# motobit.net
KiCad netlist of a schematic drawn in EAGLE
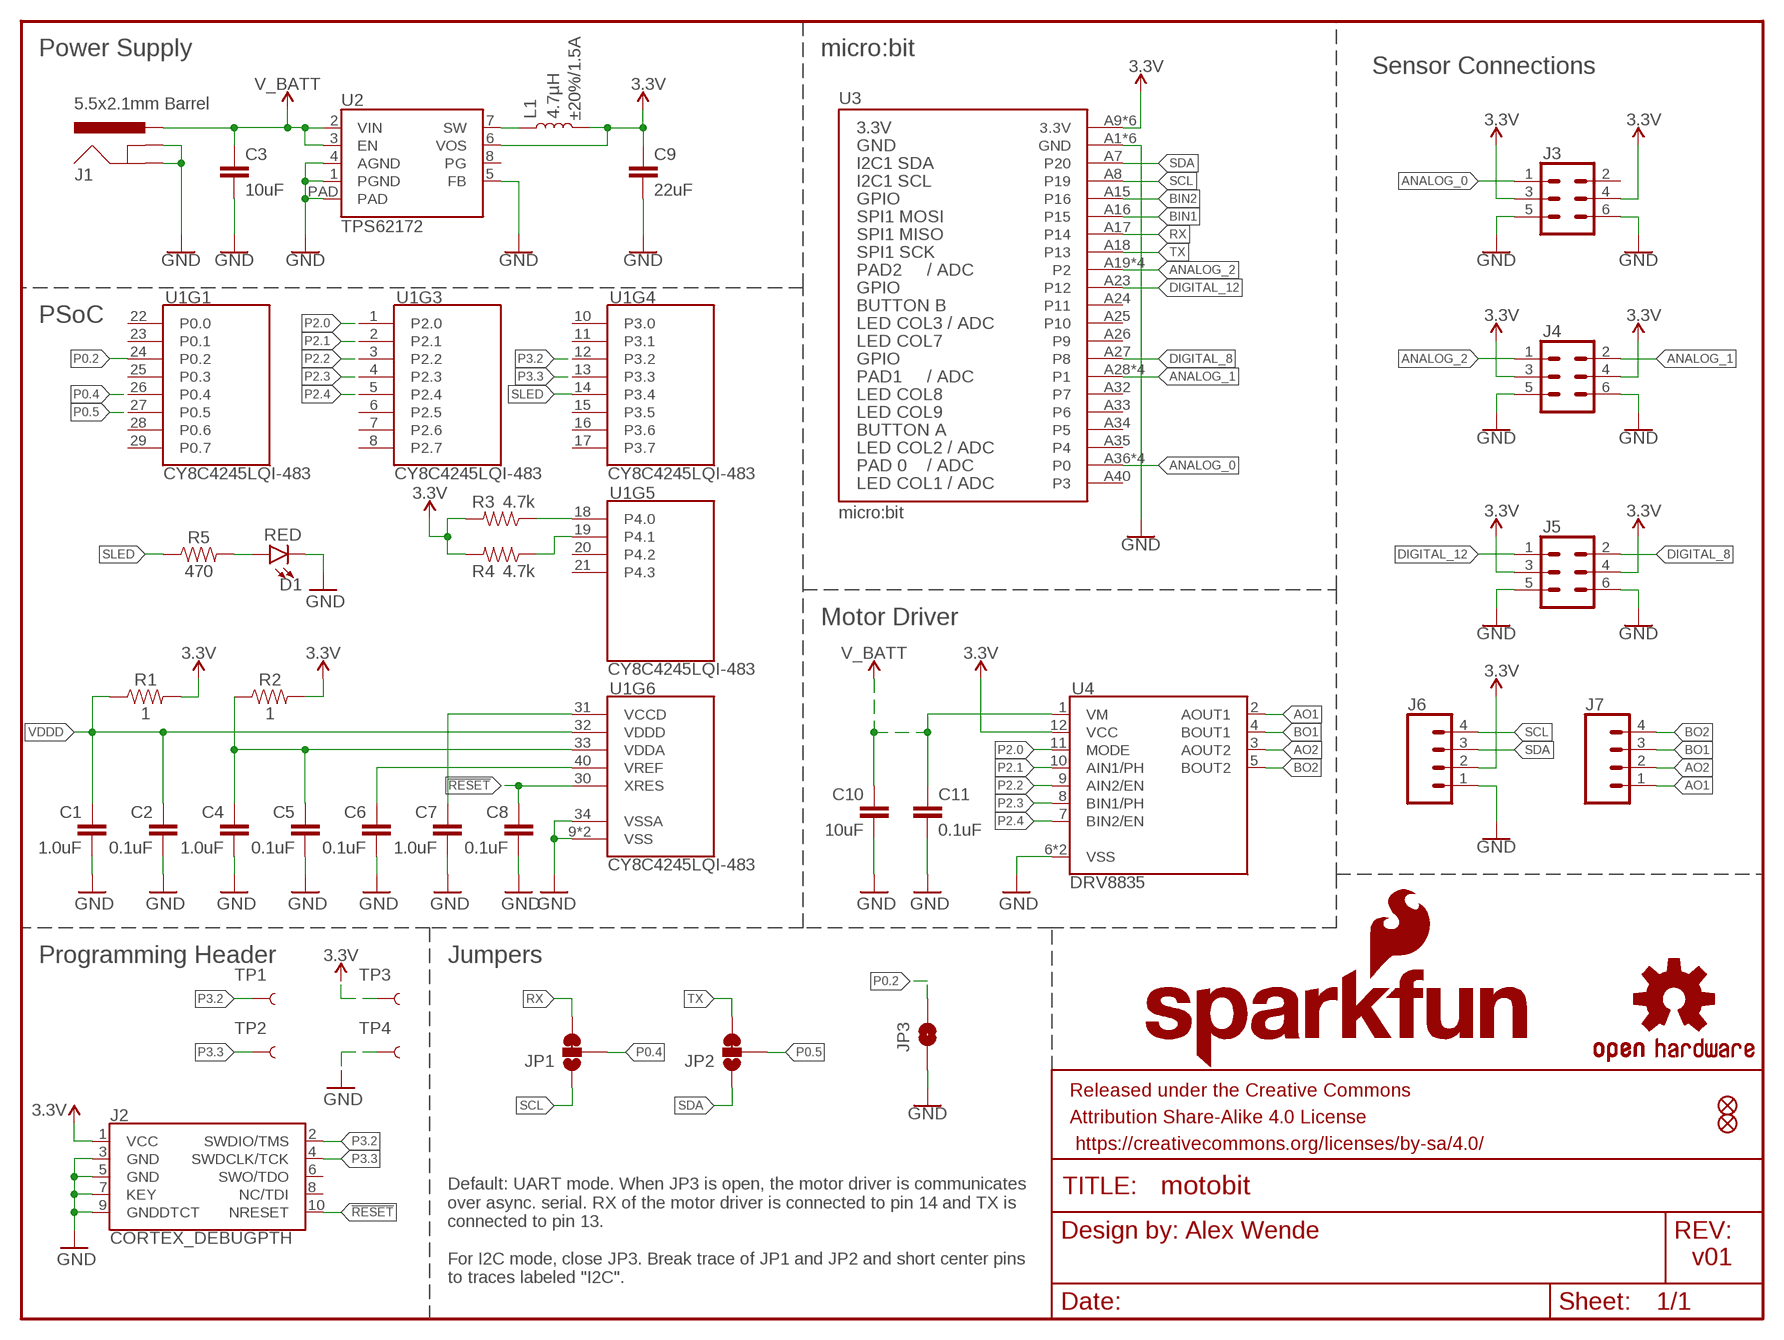
[diagram p0: schematic, sheet 1]

(export (version "E")
  (design (tool "Eeschema 10.0.6"))
  (components
    (comp (ref "C1")
      (value "1.0uF")
      (footprint "eagle-import:0603")
      (libsource (lib "eagle-import") (part "1.0UF-0603-16V-10%"))
    )
    (comp (ref "C2")
      (value "0.1uF")
      (footprint "eagle-import:0603")
      (libsource (lib "eagle-import") (part "0.1UF-0603-25V-(+80/-20%)"))
    )
    (comp (ref "C3")
      (value "10uF")
      (footprint "eagle-import:1210")
      (libsource (lib "eagle-import") (part "10UF-1210-50V-20%"))
    )
    (comp (ref "C4")
      (value "1.0uF")
      (footprint "eagle-import:0603")
      (libsource (lib "eagle-import") (part "1.0UF-0603-16V-10%"))
    )
    (comp (ref "C5")
      (value "0.1uF")
      (footprint "eagle-import:0603")
      (libsource (lib "eagle-import") (part "0.1UF-0603-25V-(+80/-20%)"))
    )
    (comp (ref "C6")
      (value "0.1uF")
      (footprint "eagle-import:0603")
      (libsource (lib "eagle-import") (part "0.1UF-0603-25V-(+80/-20%)"))
    )
    (comp (ref "C7")
      (value "1.0uF")
      (footprint "eagle-import:0603")
      (libsource (lib "eagle-import") (part "1.0UF-0603-16V-10%"))
    )
    (comp (ref "C8")
      (value "0.1uF")
      (footprint "eagle-import:0603")
      (libsource (lib "eagle-import") (part "0.1UF-0603-25V-(+80/-20%)"))
    )
    (comp (ref "C9")
      (value "22uF")
      (footprint "eagle-import:0805")
      (libsource (lib "eagle-import") (part "22UF-0805-6.3V-20%"))
    )
    (comp (ref "C10")
      (value "10uF")
      (footprint "eagle-import:1210")
      (libsource (lib "eagle-import") (part "10UF-1210-50V-20%"))
    )
    (comp (ref "C11")
      (value "0.1uF")
      (footprint "eagle-import:0603")
      (libsource (lib "eagle-import") (part "0.1UF-0603-25V-(+80/-20%)"))
    )
    (comp (ref "D1")
      (value "RED")
      (footprint "eagle-import:LED-0603")
      (libsource (lib "eagle-import") (part "LED-RED0603"))
    )
    (comp (ref "FD1")
      (value "FIDUCIALUFIDUCIAL")
      (footprint "eagle-import:FIDUCIAL-MICRO")
      (libsource (lib "eagle-import") (part "FIDUCIALUFIDUCIAL"))
    )
    (comp (ref "FD2")
      (value "FIDUCIALUFIDUCIAL")
      (footprint "eagle-import:FIDUCIAL-MICRO")
      (libsource (lib "eagle-import") (part "FIDUCIALUFIDUCIAL"))
    )
    (comp (ref "FRAME1")
      (value "FRAME-LETTER")
      (footprint "eagle-import:CREATIVE_COMMONS")
      (libsource (lib "eagle-import") (part "FRAME-LETTER"))
    )
    (comp (ref "J1")
      (value "5.5x2.1mm Barrel")
      (footprint "eagle-import:POWER_JACK_SMD")
      (libsource (lib "eagle-import") (part "POWER_JACKSMD"))
    )
    (comp (ref "J2")
      (value "CORTEX_DEBUGPTH")
      (footprint "eagle-import:2X5-PTH-1.27MM")
      (libsource (lib "eagle-import") (part "CORTEX_DEBUGPTH"))
    )
    (comp (ref "J3")
      (value "CONN_03X2FEMALE_SMD")
      (footprint "eagle-import:2X3_SMD")
      (libsource (lib "eagle-import") (part "CONN_03X2FEMALE_SMD"))
    )
    (comp (ref "J4")
      (value "CONN_03X2FEMALE_SMD")
      (footprint "eagle-import:2X3_SMD")
      (libsource (lib "eagle-import") (part "CONN_03X2FEMALE_SMD"))
    )
    (comp (ref "J5")
      (value "CONN_03X2FEMALE_SMD")
      (footprint "eagle-import:2X3_SMD")
      (libsource (lib "eagle-import") (part "CONN_03X2FEMALE_SMD"))
    )
    (comp (ref "J6")
      (value "CONN_04SMD_STRAIGHT_COMBO")
      (footprint "eagle-import:1X04_SMD_VERTICAL_COMBO")
      (libsource (lib "eagle-import") (part "CONN_04SMD_STRAIGHT_COMBO"))
    )
    (comp (ref "J7")
      (value "CONN_04SMD_RA_FEMALE")
      (footprint "eagle-import:1X04_SMD_RA_FEMALE")
      (libsource (lib "eagle-import") (part "CONN_04SMD_RA_FEMALE"))
    )
    (comp (ref "JP1")
      (value "JUMPER-SMT_3_1-NC_TRACE_SILK")
      (footprint "eagle-import:SMT-JUMPER_3_1-NC_TRACE_SILK")
      (libsource (lib "eagle-import") (part "JUMPER-SMT_3_1-NC_TRACE_SILK"))
    )
    (comp (ref "JP2")
      (value "JUMPER-SMT_3_1-NC_TRACE_SILK")
      (footprint "eagle-import:SMT-JUMPER_3_1-NC_TRACE_SILK")
      (libsource (lib "eagle-import") (part "JUMPER-SMT_3_1-NC_TRACE_SILK"))
    )
    (comp (ref "JP3")
      (value "JUMPER-SMT_2_NO_SILK")
      (footprint "eagle-import:SMT-JUMPER_2_NO_SILK")
      (libsource (lib "eagle-import") (part "JUMPER-SMT_2_NO_SILK"))
    )
    (comp (ref "L1")
      (value "4.7µH")
      (footprint "eagle-import:INDUCTOR_2.2UH")
      (libsource (lib "eagle-import") (part "INDUCTOR-VLF4012AT-2.2UH"))
    )
    (comp (ref "LOGO1")
      (value "SFE_LOGO_NAME_FLAME.2_INCH")
      (footprint "eagle-import:SFE_LOGO_NAME_FLAME_.2")
      (libsource (lib "eagle-import") (part "SFE_LOGO_NAME_FLAME.2_INCH"))
    )
    (comp (ref "LOGO2")
      (value "OSHW-LOGOM")
      (footprint "eagle-import:OSHW-LOGO-M")
      (libsource (lib "eagle-import") (part "OSHW-LOGOM"))
    )
    (comp (ref "R1")
      (value "1")
      (footprint "eagle-import:0603")
      (libsource (lib "eagle-import") (part "1OHM-0603-1/10W-1%"))
    )
    (comp (ref "R2")
      (value "1")
      (footprint "eagle-import:0603")
      (libsource (lib "eagle-import") (part "1OHM-0603-1/10W-1%"))
    )
    (comp (ref "R3")
      (value "4.7k")
      (footprint "eagle-import:0603")
      (libsource (lib "eagle-import") (part "4.7KOHM-0603-1/10W-1%"))
    )
    (comp (ref "R4")
      (value "4.7k")
      (footprint "eagle-import:0603")
      (libsource (lib "eagle-import") (part "4.7KOHM-0603-1/10W-1%"))
    )
    (comp (ref "R5")
      (value "470")
      (footprint "eagle-import:0603")
      (libsource (lib "eagle-import") (part "470OHM-0603-1/10W-1%"))
    )
    (comp (ref "TP1")
      (value "TEST-POINT3")
      (footprint "eagle-import:PAD.03X.03")
      (libsource (lib "eagle-import") (part "TEST-POINT3"))
    )
    (comp (ref "TP2")
      (value "TEST-POINT3")
      (footprint "eagle-import:PAD.03X.03")
      (libsource (lib "eagle-import") (part "TEST-POINT3"))
    )
    (comp (ref "TP3")
      (value "TEST-POINT3")
      (footprint "eagle-import:PAD.03X.03")
      (libsource (lib "eagle-import") (part "TEST-POINT3"))
    )
    (comp (ref "TP4")
      (value "TEST-POINT3")
      (footprint "eagle-import:PAD.03X.03")
      (libsource (lib "eagle-import") (part "TEST-POINT3"))
    )
    (comp (ref "U1")
      (value "CY8C4245LQI-483")
      (footprint "eagle-import:QFN-40")
      (libsource (lib "eagle-import") (part "PSOC4_4200_40QFN"))
    )
    (comp (ref "U2")
      (value "TPS62172")
      (footprint "eagle-import:WSON-8-PAD")
      (libsource (lib "eagle-import") (part "TPS62172"))
    )
    (comp (ref "U3")
      (value "micro:bit")
      (footprint "eagle-import:MICRO_BIT_RA_PTH")
      (libsource (lib "eagle-import") (part "MICRO{colon}BITLEDS_UP"))
    )
    (comp (ref "U4")
      (value "DRV8835")
      (footprint "eagle-import:WSON-12")
      (libsource (lib "eagle-import") (part "DRV883X"))
    )
  )
  (nets
    (net (code "1") (name "/~{RESET}") (class "Default")
      (node (ref "C8") (pin "1") (pinfunction "1_1") (pintype "passive"))
      (node (ref "J2") (pin "10") (pinfunction "NRESET_10") (pintype "bidirectional"))
      (node (ref "U1") (pin "30") (pinfunction "XRES_30") (pintype "bidirectional"))
    )
    (net (code "2") (name "3.3V") (class "Default")
      (node (ref "C9") (pin "1") (pinfunction "1_1") (pintype "passive"))
      (node (ref "J2") (pin "1") (pinfunction "VCC_1") (pintype "bidirectional"))
      (node (ref "J3") (pin "3") (pinfunction "3_3") (pintype "bidirectional"))
      (node (ref "J3") (pin "4") (pinfunction "4_4") (pintype "bidirectional"))
      (node (ref "J4") (pin "3") (pinfunction "3_3") (pintype "bidirectional"))
      (node (ref "J4") (pin "4") (pinfunction "4_4") (pintype "bidirectional"))
      (node (ref "J5") (pin "3") (pinfunction "3_3") (pintype "bidirectional"))
      (node (ref "J5") (pin "4") (pinfunction "4_4") (pintype "bidirectional"))
      (node (ref "J6") (pin "2") (pinfunction "2_2") (pintype "passive"))
      (node (ref "L1") (pin "P$2") (pinfunction "2_P$2") (pintype "passive"))
      (node (ref "R1") (pin "2") (pinfunction "2_2") (pintype "passive"))
      (node (ref "R2") (pin "2") (pinfunction "2_2") (pintype "passive"))
      (node (ref "R3") (pin "2") (pinfunction "2_2") (pintype "passive"))
      (node (ref "R4") (pin "2") (pinfunction "2_2") (pintype "passive"))
      (node (ref "TP3") (pin "P$1") (pinfunction "1_P$1") (pintype "bidirectional"))
      (node (ref "U2") (pin "6") (pinfunction "VOS_6") (pintype "bidirectional"))
      (node (ref "U3") (pin "A10") (pinfunction "3.3V_A10") (pintype "bidirectional"))
      (node (ref "U3") (pin "A11") (pinfunction "3.3V_A11") (pintype "bidirectional"))
      (node (ref "U3") (pin "A12") (pinfunction "3.3V_A12") (pintype "bidirectional"))
      (node (ref "U3") (pin "A13") (pinfunction "3.3V_A13") (pintype "bidirectional"))
      (node (ref "U3") (pin "A14") (pinfunction "3.3V_A14") (pintype "bidirectional"))
      (node (ref "U3") (pin "A9") (pinfunction "3.3V_A9") (pintype "bidirectional"))
      (node (ref "U4") (pin "12") (pinfunction "VCC_12") (pintype "bidirectional"))
    )
    (net (code "3") (name "ANALOG_0") (class "Default")
      (node (ref "J3") (pin "1") (pinfunction "1_1") (pintype "bidirectional"))
      (node (ref "U3") (pin "A36") (pinfunction "P0_A36") (pintype "bidirectional"))
      (node (ref "U3") (pin "A37") (pinfunction "P0_A37") (pintype "bidirectional"))
      (node (ref "U3") (pin "A38") (pinfunction "P0_A38") (pintype "bidirectional"))
      (node (ref "U3") (pin "A39") (pinfunction "P0_A39") (pintype "bidirectional"))
    )
    (net (code "4") (name "ANALOG_1") (class "Default")
      (node (ref "J4") (pin "2") (pinfunction "2_2") (pintype "bidirectional"))
      (node (ref "U3") (pin "A28") (pinfunction "P1_A28") (pintype "bidirectional"))
      (node (ref "U3") (pin "A29") (pinfunction "P1_A29") (pintype "bidirectional"))
      (node (ref "U3") (pin "A30") (pinfunction "P1_A30") (pintype "bidirectional"))
      (node (ref "U3") (pin "A31") (pinfunction "P1_A31") (pintype "bidirectional"))
    )
    (net (code "5") (name "ANALOG_2") (class "Default")
      (node (ref "J4") (pin "1") (pinfunction "1_1") (pintype "bidirectional"))
      (node (ref "U3") (pin "A19") (pinfunction "P2_A19") (pintype "bidirectional"))
      (node (ref "U3") (pin "A20") (pinfunction "P2_A20") (pintype "bidirectional"))
      (node (ref "U3") (pin "A21") (pinfunction "P2_A21") (pintype "bidirectional"))
      (node (ref "U3") (pin "A22") (pinfunction "P2_A22") (pintype "bidirectional"))
    )
    (net (code "6") (name "AO1") (class "Default")
      (node (ref "J7") (pin "1") (pinfunction "1_1") (pintype "passive"))
      (node (ref "U4") (pin "2") (pinfunction "AOUT1_2") (pintype "bidirectional"))
    )
    (net (code "7") (name "AO2") (class "Default")
      (node (ref "J7") (pin "2") (pinfunction "2_2") (pintype "passive"))
      (node (ref "U4") (pin "3") (pinfunction "AOUT2_3") (pintype "bidirectional"))
    )
    (net (code "8") (name "BIN1") (class "Default")
      (node (ref "U3") (pin "A16") (pinfunction "P15_A16") (pintype "bidirectional"))
    )
    (net (code "9") (name "BIN2") (class "Default")
      (node (ref "U3") (pin "A15") (pinfunction "P16_A15") (pintype "bidirectional"))
    )
    (net (code "10") (name "BO1") (class "Default")
      (node (ref "J7") (pin "3") (pinfunction "3_3") (pintype "passive"))
      (node (ref "U4") (pin "4") (pinfunction "BOUT1_4") (pintype "bidirectional"))
    )
    (net (code "11") (name "BO2") (class "Default")
      (node (ref "J7") (pin "4") (pinfunction "4_4") (pintype "passive"))
      (node (ref "U4") (pin "5") (pinfunction "BOUT2_5") (pintype "bidirectional"))
    )
    (net (code "12") (name "DIGITAL_8") (class "Default")
      (node (ref "J5") (pin "2") (pinfunction "2_2") (pintype "bidirectional"))
      (node (ref "U3") (pin "A27") (pinfunction "P8_A27") (pintype "bidirectional"))
    )
    (net (code "13") (name "DIGITAL_12") (class "Default")
      (node (ref "J5") (pin "1") (pinfunction "1_1") (pintype "bidirectional"))
      (node (ref "U3") (pin "A23") (pinfunction "P12_A23") (pintype "bidirectional"))
    )
    (net (code "14") (name "GND") (class "Default")
      (node (ref "C1") (pin "2") (pinfunction "2_2") (pintype "passive"))
      (node (ref "C10") (pin "2") (pinfunction "2_2") (pintype "passive"))
      (node (ref "C11") (pin "2") (pinfunction "2_2") (pintype "passive"))
      (node (ref "C2") (pin "2") (pinfunction "2_2") (pintype "passive"))
      (node (ref "C3") (pin "2") (pinfunction "2_2") (pintype "passive"))
      (node (ref "C4") (pin "2") (pinfunction "2_2") (pintype "passive"))
      (node (ref "C5") (pin "2") (pinfunction "2_2") (pintype "passive"))
      (node (ref "C6") (pin "2") (pinfunction "2_2") (pintype "passive"))
      (node (ref "C7") (pin "2") (pinfunction "2_2") (pintype "passive"))
      (node (ref "C8") (pin "2") (pinfunction "2_2") (pintype "passive"))
      (node (ref "C9") (pin "2") (pinfunction "2_2") (pintype "passive"))
      (node (ref "D1") (pin "C") (pinfunction "C_C") (pintype "passive"))
      (node (ref "J1") (pin "GND") (pinfunction "GNDBREAK_GND") (pintype "bidirectional"))
      (node (ref "J1") (pin "P$4") (pinfunction "GND_P$4") (pintype "bidirectional"))
      (node (ref "J2") (pin "3") (pinfunction "GND_3") (pintype "bidirectional"))
      (node (ref "J2") (pin "5") (pinfunction "GND_5") (pintype "bidirectional"))
      (node (ref "J2") (pin "7") (pinfunction "KEY_7") (pintype "bidirectional"))
      (node (ref "J2") (pin "9") (pinfunction "GNDDTCT_9") (pintype "bidirectional"))
      (node (ref "J3") (pin "5") (pinfunction "5_5") (pintype "bidirectional"))
      (node (ref "J3") (pin "6") (pinfunction "6_6") (pintype "bidirectional"))
      (node (ref "J4") (pin "5") (pinfunction "5_5") (pintype "bidirectional"))
      (node (ref "J4") (pin "6") (pinfunction "6_6") (pintype "bidirectional"))
      (node (ref "J5") (pin "5") (pinfunction "5_5") (pintype "bidirectional"))
      (node (ref "J5") (pin "6") (pinfunction "6_6") (pintype "bidirectional"))
      (node (ref "J6") (pin "1") (pinfunction "1_1") (pintype "passive"))
      (node (ref "JP3") (pin "1") (pinfunction "1_1") (pintype "passive"))
      (node (ref "TP4") (pin "P$1") (pinfunction "1_P$1") (pintype "bidirectional"))
      (node (ref "U1") (pin "34") (pinfunction "VSSA_34") (pintype "bidirectional"))
      (node (ref "U1") (pin "9") (pinfunction "VSS_9") (pintype "bidirectional"))
      (node (ref "U1") (pin "EP") (pinfunction "VSS_EP") (pintype "bidirectional"))
      (node (ref "U2") (pin "1") (pinfunction "PGND_1") (pintype "bidirectional"))
      (node (ref "U2") (pin "4") (pinfunction "AGND_4") (pintype "bidirectional"))
      (node (ref "U2") (pin "5") (pinfunction "FB_5") (pintype "bidirectional"))
      (node (ref "U2") (pin "PAD") (pinfunction "PAD_PAD") (pintype "bidirectional"))
      (node (ref "U3") (pin "A1") (pinfunction "GND_A1") (pintype "bidirectional"))
      (node (ref "U3") (pin "A2") (pinfunction "GND_A2") (pintype "bidirectional"))
      (node (ref "U3") (pin "A3") (pinfunction "GND_A3") (pintype "bidirectional"))
      (node (ref "U3") (pin "A4") (pinfunction "GND_A4") (pintype "bidirectional"))
      (node (ref "U3") (pin "A5") (pinfunction "GND_A5") (pintype "bidirectional"))
      (node (ref "U3") (pin "A6") (pinfunction "GND_A6") (pintype "bidirectional"))
      (node (ref "U4") (pin "6") (pinfunction "VSS_6") (pintype "bidirectional"))
      (node (ref "U4") (pin "PAD") (pinfunction "VSS_PAD") (pintype "bidirectional"))
    )
    (net (code "15") (name "Net-(D1-PadA)") (class "Default")
      (node (ref "D1") (pin "A") (pinfunction "A_A") (pintype "passive"))
      (node (ref "R5") (pin "2") (pinfunction "2_2") (pintype "passive"))
    )
    (net (code "16") (name "Net-(L1-1)") (class "Default")
      (node (ref "L1") (pin "P$1") (pinfunction "1_P$1") (pintype "passive"))
      (node (ref "U2") (pin "7") (pinfunction "SW_7") (pintype "bidirectional"))
    )
    (net (code "17") (name "Net-(U1E-P4.0)") (class "Default")
      (node (ref "R3") (pin "1") (pinfunction "1_1") (pintype "passive"))
      (node (ref "U1") (pin "18") (pinfunction "P4.0_18") (pintype "bidirectional"))
    )
    (net (code "18") (name "Net-(U1E-P4.1)") (class "Default")
      (node (ref "R4") (pin "1") (pinfunction "1_1") (pintype "passive"))
      (node (ref "U1") (pin "19") (pinfunction "P4.1_19") (pintype "bidirectional"))
    )
    (net (code "19") (name "Net-(U1F-VCCD)") (class "Default")
      (node (ref "C7") (pin "1") (pinfunction "1_1") (pintype "passive"))
      (node (ref "U1") (pin "31") (pinfunction "VCCD_31") (pintype "bidirectional"))
    )
    (net (code "20") (name "Net-(U1F-VDDA)") (class "Default")
      (node (ref "C4") (pin "1") (pinfunction "1_1") (pintype "passive"))
      (node (ref "C5") (pin "1") (pinfunction "1_1") (pintype "passive"))
      (node (ref "R2") (pin "1") (pinfunction "1_1") (pintype "passive"))
      (node (ref "U1") (pin "33") (pinfunction "VDDA_33") (pintype "bidirectional"))
    )
    (net (code "21") (name "Net-(U1F-VREF)") (class "Default")
      (node (ref "C6") (pin "1") (pinfunction "1_1") (pintype "passive"))
      (node (ref "U1") (pin "40") (pinfunction "VREF_40") (pintype "bidirectional"))
    )
    (net (code "22") (name "P0.2") (class "Default")
      (node (ref "JP3") (pin "2") (pinfunction "2_2") (pintype "passive"))
      (node (ref "U1") (pin "24") (pinfunction "P0.2_24") (pintype "bidirectional"))
    )
    (net (code "23") (name "P0.4") (class "Default")
      (node (ref "JP1") (pin "2") (pinfunction "2_2") (pintype "passive"))
      (node (ref "U1") (pin "26") (pinfunction "P0.4_26") (pintype "bidirectional"))
    )
    (net (code "24") (name "P0.5") (class "Default")
      (node (ref "JP2") (pin "2") (pinfunction "2_2") (pintype "passive"))
      (node (ref "U1") (pin "27") (pinfunction "P0.5_27") (pintype "bidirectional"))
    )
    (net (code "25") (name "P2.0") (class "Default")
      (node (ref "U1") (pin "1") (pinfunction "P2.0_1") (pintype "bidirectional"))
      (node (ref "U4") (pin "11") (pinfunction "MODE_11") (pintype "bidirectional"))
    )
    (net (code "26") (name "P2.1") (class "Default")
      (node (ref "U1") (pin "2") (pinfunction "P2.1_2") (pintype "bidirectional"))
      (node (ref "U4") (pin "10") (pinfunction "AIN1/PH_10") (pintype "bidirectional"))
    )
    (net (code "27") (name "P2.2") (class "Default")
      (node (ref "U1") (pin "3") (pinfunction "P2.2_3") (pintype "bidirectional"))
      (node (ref "U4") (pin "9") (pinfunction "AIN2/EN_9") (pintype "bidirectional"))
    )
    (net (code "28") (name "P2.3") (class "Default")
      (node (ref "U1") (pin "4") (pinfunction "P2.3_4") (pintype "bidirectional"))
      (node (ref "U4") (pin "8") (pinfunction "BIN1/PH_8") (pintype "bidirectional"))
    )
    (net (code "29") (name "P2.4") (class "Default")
      (node (ref "U1") (pin "5") (pinfunction "P2.4_5") (pintype "bidirectional"))
      (node (ref "U4") (pin "7") (pinfunction "BIN2/EN_7") (pintype "bidirectional"))
    )
    (net (code "30") (name "P3.2") (class "Default")
      (node (ref "J2") (pin "2") (pinfunction "SWDIO/TMS_2") (pintype "bidirectional"))
      (node (ref "TP1") (pin "P$1") (pinfunction "1_P$1") (pintype "bidirectional"))
      (node (ref "U1") (pin "12") (pinfunction "P3.2_12") (pintype "bidirectional"))
    )
    (net (code "31") (name "P3.3") (class "Default")
      (node (ref "J2") (pin "4") (pinfunction "SWDCLK/TCK_4") (pintype "bidirectional"))
      (node (ref "TP2") (pin "P$1") (pinfunction "1_P$1") (pintype "bidirectional"))
      (node (ref "U1") (pin "13") (pinfunction "P3.3_13") (pintype "bidirectional"))
    )
    (net (code "32") (name "RX") (class "Default")
      (node (ref "JP1") (pin "3") (pinfunction "3_3") (pintype "passive"))
      (node (ref "U3") (pin "A17") (pinfunction "P14_A17") (pintype "bidirectional"))
    )
    (net (code "33") (name "SCL") (class "Default")
      (node (ref "J6") (pin "4") (pinfunction "4_4") (pintype "passive"))
      (node (ref "JP1") (pin "1") (pinfunction "1_1") (pintype "passive"))
      (node (ref "U3") (pin "A8") (pinfunction "P19_A8") (pintype "bidirectional"))
    )
    (net (code "34") (name "SDA") (class "Default")
      (node (ref "J6") (pin "3") (pinfunction "3_3") (pintype "passive"))
      (node (ref "JP2") (pin "1") (pinfunction "1_1") (pintype "passive"))
      (node (ref "U3") (pin "A7") (pinfunction "P20_A7") (pintype "bidirectional"))
    )
    (net (code "35") (name "SLED") (class "Default")
      (node (ref "R5") (pin "1") (pinfunction "1_1") (pintype "passive"))
      (node (ref "U1") (pin "14") (pinfunction "P3.4_14") (pintype "bidirectional"))
    )
    (net (code "36") (name "TX") (class "Default")
      (node (ref "JP2") (pin "3") (pinfunction "3_3") (pintype "passive"))
      (node (ref "U3") (pin "A18") (pinfunction "P13_A18") (pintype "bidirectional"))
    )
    (net (code "37") (name "VDDD") (class "Default")
      (node (ref "C1") (pin "1") (pinfunction "1_1") (pintype "passive"))
      (node (ref "C2") (pin "1") (pinfunction "1_1") (pintype "passive"))
      (node (ref "R1") (pin "1") (pinfunction "1_1") (pintype "passive"))
      (node (ref "U1") (pin "32") (pinfunction "VDDD_32") (pintype "bidirectional"))
    )
    (net (code "38") (name "V_BATT") (class "Default")
      (node (ref "C10") (pin "1") (pinfunction "1_1") (pintype "passive"))
      (node (ref "C11") (pin "1") (pinfunction "1_1") (pintype "passive"))
      (node (ref "C3") (pin "1") (pinfunction "1_1") (pintype "passive"))
      (node (ref "J1") (pin "VIN0") (pinfunction "PWR_VIN0") (pintype "bidirectional"))
      (node (ref "U2") (pin "2") (pinfunction "VIN_2") (pintype "bidirectional"))
      (node (ref "U2") (pin "3") (pinfunction "EN_3") (pintype "bidirectional"))
      (node (ref "U4") (pin "1") (pinfunction "VM_1") (pintype "bidirectional"))
    )
    (net (code "39") (name "unconnected-(J2-NC{slash}TDI-Pad8)") (class "Default")
      (node (ref "J2") (pin "8") (pinfunction "NC/TDI_8") (pintype "bidirectional"))
    )
    (net (code "40") (name "unconnected-(J2-SWO{slash}TDO-Pad6)") (class "Default")
      (node (ref "J2") (pin "6") (pinfunction "SWO/TDO_6") (pintype "bidirectional"))
    )
    (net (code "41") (name "unconnected-(J3-Pad2)") (class "Default")
      (node (ref "J3") (pin "2") (pinfunction "2_2") (pintype "bidirectional"))
    )
    (net (code "42") (name "unconnected-(U1A-P0.0-Pad22)") (class "Default")
      (node (ref "U1") (pin "22") (pinfunction "P0.0_22") (pintype "bidirectional"))
    )
    (net (code "43") (name "unconnected-(U1A-P0.1-Pad23)") (class "Default")
      (node (ref "U1") (pin "23") (pinfunction "P0.1_23") (pintype "bidirectional"))
    )
    (net (code "44") (name "unconnected-(U1A-P0.3-Pad25)") (class "Default")
      (node (ref "U1") (pin "25") (pinfunction "P0.3_25") (pintype "bidirectional"))
    )
    (net (code "45") (name "unconnected-(U1A-P0.6-Pad28)") (class "Default")
      (node (ref "U1") (pin "28") (pinfunction "P0.6_28") (pintype "bidirectional"))
    )
    (net (code "46") (name "unconnected-(U1A-P0.7-Pad29)") (class "Default")
      (node (ref "U1") (pin "29") (pinfunction "P0.7_29") (pintype "bidirectional"))
    )
    (net (code "47") (name "unconnected-(U1C-P2.5-Pad6)") (class "Default")
      (node (ref "U1") (pin "6") (pinfunction "P2.5_6") (pintype "bidirectional"))
    )
    (net (code "48") (name "unconnected-(U1C-P2.6-Pad7)") (class "Default")
      (node (ref "U1") (pin "7") (pinfunction "P2.6_7") (pintype "bidirectional"))
    )
    (net (code "49") (name "unconnected-(U1C-P2.7-Pad8)") (class "Default")
      (node (ref "U1") (pin "8") (pinfunction "P2.7_8") (pintype "bidirectional"))
    )
    (net (code "50") (name "unconnected-(U1D-P3.0-Pad10)") (class "Default")
      (node (ref "U1") (pin "10") (pinfunction "P3.0_10") (pintype "bidirectional"))
    )
    (net (code "51") (name "unconnected-(U1D-P3.1-Pad11)") (class "Default")
      (node (ref "U1") (pin "11") (pinfunction "P3.1_11") (pintype "bidirectional"))
    )
    (net (code "52") (name "unconnected-(U1D-P3.5-Pad15)") (class "Default")
      (node (ref "U1") (pin "15") (pinfunction "P3.5_15") (pintype "bidirectional"))
    )
    (net (code "53") (name "unconnected-(U1D-P3.6-Pad16)") (class "Default")
      (node (ref "U1") (pin "16") (pinfunction "P3.6_16") (pintype "bidirectional"))
    )
    (net (code "54") (name "unconnected-(U1D-P3.7-Pad17)") (class "Default")
      (node (ref "U1") (pin "17") (pinfunction "P3.7_17") (pintype "bidirectional"))
    )
    (net (code "55") (name "unconnected-(U1E-P4.2-Pad20)") (class "Default")
      (node (ref "U1") (pin "20") (pinfunction "P4.2_20") (pintype "bidirectional"))
    )
    (net (code "56") (name "unconnected-(U1E-P4.3-Pad21)") (class "Default")
      (node (ref "U1") (pin "21") (pinfunction "P4.3_21") (pintype "bidirectional"))
    )
    (net (code "57") (name "unconnected-(U2-PG-Pad8)") (class "Default")
      (node (ref "U2") (pin "8") (pinfunction "PG_8") (pintype "bidirectional"))
    )
    (net (code "58") (name "unconnected-(U3-P3-PadA40)") (class "Default")
      (node (ref "U3") (pin "A40") (pinfunction "P3_A40") (pintype "bidirectional"))
    )
    (net (code "59") (name "unconnected-(U3-P4-PadA35)") (class "Default")
      (node (ref "U3") (pin "A35") (pinfunction "P4_A35") (pintype "bidirectional"))
    )
    (net (code "60") (name "unconnected-(U3-P5-PadA34)") (class "Default")
      (node (ref "U3") (pin "A34") (pinfunction "P5_A34") (pintype "bidirectional"))
    )
    (net (code "61") (name "unconnected-(U3-P6-PadA33)") (class "Default")
      (node (ref "U3") (pin "A33") (pinfunction "P6_A33") (pintype "bidirectional"))
    )
    (net (code "62") (name "unconnected-(U3-P7-PadA32)") (class "Default")
      (node (ref "U3") (pin "A32") (pinfunction "P7_A32") (pintype "bidirectional"))
    )
    (net (code "63") (name "unconnected-(U3-P9-PadA26)") (class "Default")
      (node (ref "U3") (pin "A26") (pinfunction "P9_A26") (pintype "bidirectional"))
    )
    (net (code "64") (name "unconnected-(U3-P10-PadA25)") (class "Default")
      (node (ref "U3") (pin "A25") (pinfunction "P10_A25") (pintype "bidirectional"))
    )
    (net (code "65") (name "unconnected-(U3-P11-PadA24)") (class "Default")
      (node (ref "U3") (pin "A24") (pinfunction "P11_A24") (pintype "bidirectional"))
    )
  )
)
